# Sheet_1_2023-06-20.net
KiCad netlist of a schematic drawn in Altium Designer
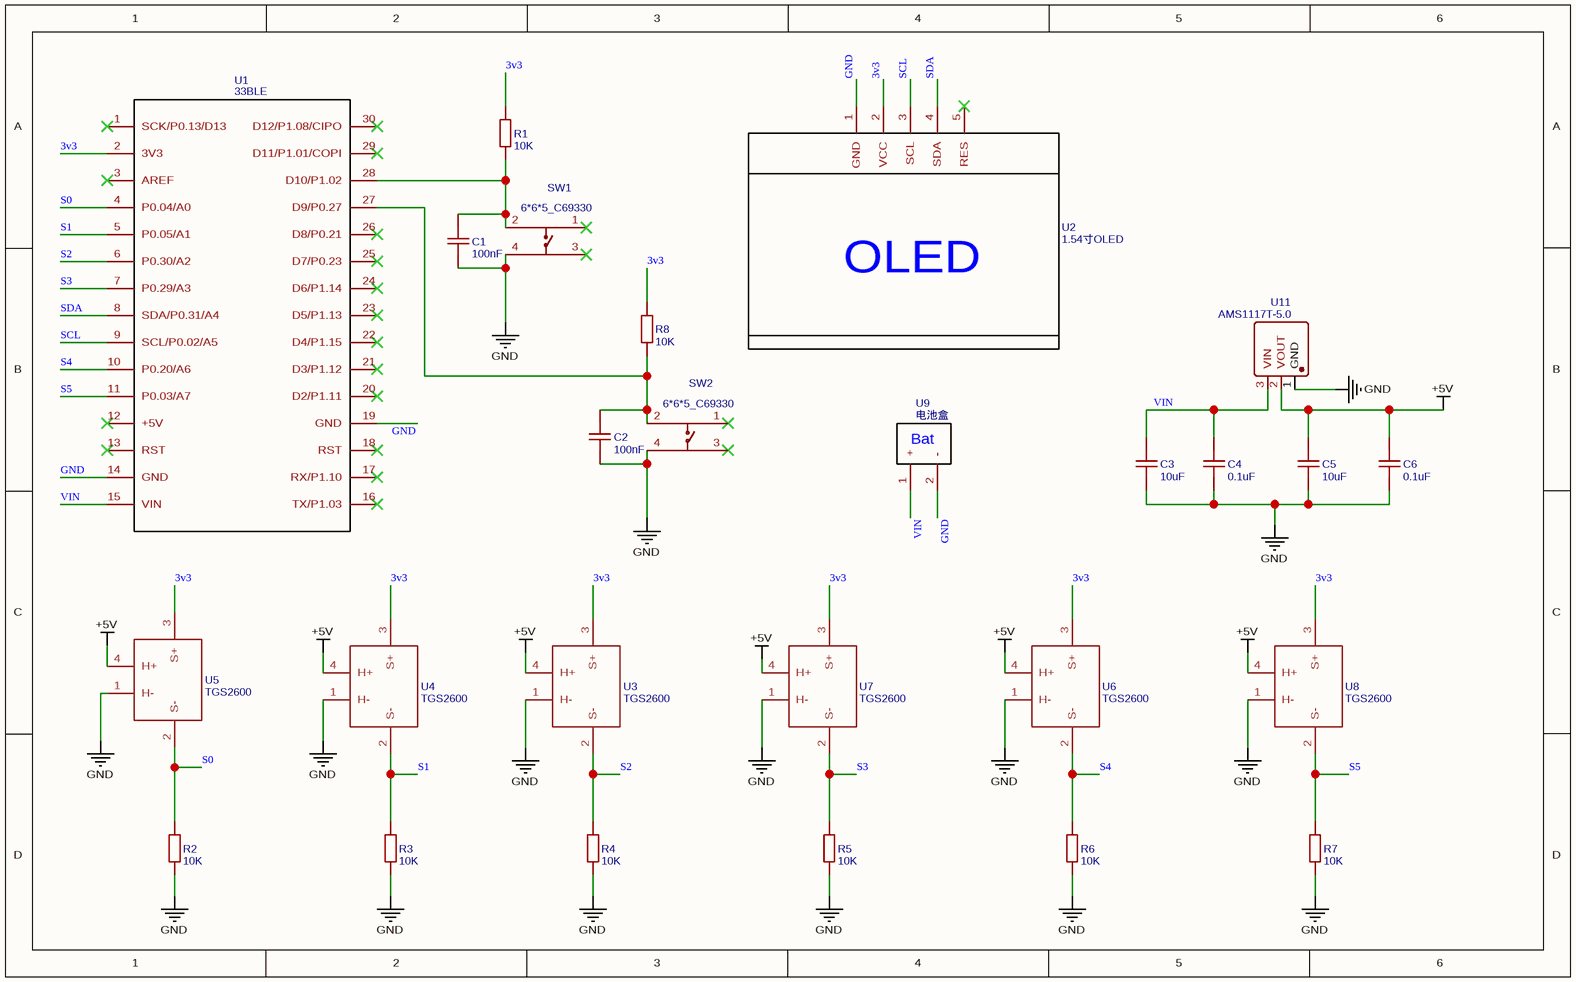
[diagram p0: Sheet_1_2023-06-20.schdoc]

(export (version "E")
  (design (tool "Eeschema 10.0.6"))
  (components
    (comp (ref "C1")
      (value "100nF")
      (fields
        (field (name "BOM_SUPPLIER PART") "C366739")
        (field (name "BOM_MANUFACTURER PART") "F06F1B104MQ0T0SHN0")
        (field (name "CONTRIBUTOR") "LCSC")
      )
      (libsource (lib "altium-import") (part "root_1_100nF_"))
    )
    (comp (ref "C2")
      (value "100nF")
      (fields
        (field (name "BOM_SUPPLIER PART") "C366739")
        (field (name "BOM_MANUFACTURER PART") "F06F1B104MQ0T0SHN0")
        (field (name "CONTRIBUTOR") "LCSC")
      )
      (libsource (lib "altium-import") (part "root_1_100nF_"))
    )
    (comp (ref "C3")
      (value "10uF")
      (fields
        (field (name "BOM_SUPPLIER PART") "C366739")
        (field (name "BOM_MANUFACTURER PART") "F06F1B104MQ0T0SHN0")
        (field (name "CONTRIBUTOR") "LCSC")
      )
      (libsource (lib "altium-import") (part "root_1_10uF_"))
    )
    (comp (ref "C4")
      (value "0.1uF")
      (fields
        (field (name "BOM_SUPPLIER PART") "C366739")
        (field (name "BOM_MANUFACTURER PART") "F06F1B104MQ0T0SHN0")
        (field (name "CONTRIBUTOR") "LCSC")
      )
      (libsource (lib "altium-import") (part "root_1_0.1uF_"))
    )
    (comp (ref "C5")
      (value "10uF")
      (fields
        (field (name "BOM_SUPPLIER PART") "C366739")
        (field (name "BOM_MANUFACTURER PART") "F06F1B104MQ0T0SHN0")
        (field (name "CONTRIBUTOR") "LCSC")
      )
      (libsource (lib "altium-import") (part "root_1_10uF_"))
    )
    (comp (ref "C6")
      (value "0.1uF")
      (fields
        (field (name "BOM_SUPPLIER PART") "C366739")
        (field (name "BOM_MANUFACTURER PART") "F06F1B104MQ0T0SHN0")
        (field (name "CONTRIBUTOR") "LCSC")
      )
      (libsource (lib "altium-import") (part "root_1_0.1uF_"))
    )
    (comp (ref "R1")
      (value "10K")
      (fields
        (field (name "BOM_SUPPLIER PART") "C176401")
        (field (name "BOM_MANUFACTURER PART") "MFR1WSJT-52-10K")
        (field (name "CONTRIBUTOR") "LCSC")
      )
      (libsource (lib "altium-import") (part "root_1_10K_"))
    )
    (comp (ref "R2")
      (value "10K")
      (fields
        (field (name "BOM_SUPPLIER PART") "C176401")
        (field (name "BOM_MANUFACTURER PART") "MFR1WSJT-52-10K")
        (field (name "CONTRIBUTOR") "LCSC")
      )
      (libsource (lib "altium-import") (part "root_1_10K_"))
    )
    (comp (ref "R3")
      (value "10K")
      (fields
        (field (name "BOM_SUPPLIER PART") "C176401")
        (field (name "BOM_MANUFACTURER PART") "MFR1WSJT-52-10K")
        (field (name "CONTRIBUTOR") "LCSC")
      )
      (libsource (lib "altium-import") (part "root_1_10K_"))
    )
    (comp (ref "R4")
      (value "10K")
      (fields
        (field (name "BOM_SUPPLIER PART") "C176401")
        (field (name "BOM_MANUFACTURER PART") "MFR1WSJT-52-10K")
        (field (name "CONTRIBUTOR") "LCSC")
      )
      (libsource (lib "altium-import") (part "root_1_10K_"))
    )
    (comp (ref "R5")
      (value "10K")
      (fields
        (field (name "BOM_SUPPLIER PART") "C176401")
        (field (name "BOM_MANUFACTURER PART") "MFR1WSJT-52-10K")
        (field (name "CONTRIBUTOR") "LCSC")
      )
      (libsource (lib "altium-import") (part "root_1_10K_"))
    )
    (comp (ref "R6")
      (value "10K")
      (fields
        (field (name "BOM_SUPPLIER PART") "C176401")
        (field (name "BOM_MANUFACTURER PART") "MFR1WSJT-52-10K")
        (field (name "CONTRIBUTOR") "LCSC")
      )
      (libsource (lib "altium-import") (part "root_1_10K_"))
    )
    (comp (ref "R7")
      (value "10K")
      (fields
        (field (name "BOM_SUPPLIER PART") "C176401")
        (field (name "BOM_MANUFACTURER PART") "MFR1WSJT-52-10K")
        (field (name "CONTRIBUTOR") "LCSC")
      )
      (libsource (lib "altium-import") (part "root_1_10K_"))
    )
    (comp (ref "R8")
      (value "10K")
      (fields
        (field (name "BOM_SUPPLIER PART") "C176401")
        (field (name "BOM_MANUFACTURER PART") "MFR1WSJT-52-10K")
        (field (name "CONTRIBUTOR") "LCSC")
      )
      (libsource (lib "altium-import") (part "root_1_10K_"))
    )
    (comp (ref "SW1")
      (value "6*6*5_C69330")
      (fields
        (field (name "BOM_MANUFACTURER PART") "6*6*5 直插环保260G 耐温复银")
        (field (name "BOM_SUPPLIER PART") "C69330")
      )
      (libsource (lib "altium-import") (part "root_2_6*6*5_C69330_"))
    )
    (comp (ref "SW2")
      (value "6*6*5_C69330")
      (fields
        (field (name "BOM_MANUFACTURER PART") "6*6*5 直插环保260G 耐温复银")
        (field (name "BOM_SUPPLIER PART") "C69330")
      )
      (libsource (lib "altium-import") (part "root_2_6*6*5_C69330_"))
    )
    (comp (ref "U1")
      (value "33BLE")
      (fields (field (name "CONTRIBUTOR") "jlu_gty"))
      (libsource (lib "altium-import") (part "root_0_33BLE_"))
    )
    (comp (ref "U2")
      (value "1.54寸OLED")
      (fields (field (name "CONTRIBUTOR") "Guest"))
      (libsource (lib "altium-import") (part "root_0_1.54寸OLED_"))
    )
    (comp (ref "U3")
      (value "TGS2600")
      (fields (field (name "BOM_SUPPLIER PART") "C9900008686") (field (name "CONTRIBUTOR") "LCSC"))
      (libsource (lib "altium-import") (part "root_0_TGS2600_"))
    )
    (comp (ref "U4")
      (value "TGS2600")
      (fields (field (name "BOM_SUPPLIER PART") "C9900008686") (field (name "CONTRIBUTOR") "LCSC"))
      (libsource (lib "altium-import") (part "root_0_TGS2600_"))
    )
    (comp (ref "U5")
      (value "TGS2600")
      (fields (field (name "BOM_SUPPLIER PART") "C9900008686") (field (name "CONTRIBUTOR") "LCSC"))
      (libsource (lib "altium-import") (part "root_0_TGS2600_"))
    )
    (comp (ref "U6")
      (value "TGS2600")
      (fields (field (name "BOM_SUPPLIER PART") "C9900008686") (field (name "CONTRIBUTOR") "LCSC"))
      (libsource (lib "altium-import") (part "root_0_TGS2600_"))
    )
    (comp (ref "U7")
      (value "TGS2600")
      (fields (field (name "BOM_SUPPLIER PART") "C9900008686") (field (name "CONTRIBUTOR") "LCSC"))
      (libsource (lib "altium-import") (part "root_0_TGS2600_"))
    )
    (comp (ref "U8")
      (value "TGS2600")
      (fields (field (name "BOM_SUPPLIER PART") "C9900008686") (field (name "CONTRIBUTOR") "LCSC"))
      (libsource (lib "altium-import") (part "root_0_TGS2600_"))
    )
    (comp (ref "U9")
      (value "电池盒")
      (fields (field (name "CONTRIBUTOR") "JLU_GTY"))
      (libsource (lib "altium-import") (part "root_0_电池盒_"))
    )
    (comp (ref "U11")
      (value "AMS1117T-5.0")
      (fields (field (name "BOM_SUPPLIER PART") "C498134") (field (name "CONTRIBUTOR") "LCSC"))
      (libsource (lib "altium-import") (part "root_1_AMS1117T-5.0_"))
    )
  )
  (nets
    (net (code "1") (name "+5V") (class "Default")
      (node (ref "C5") (pin "2") (pinfunction "2_2") (pintype "passive"))
      (node (ref "C6") (pin "2") (pinfunction "2_2") (pintype "passive"))
      (node (ref "U11") (pin "2") (pinfunction "VOUT_2") (pintype "passive"))
      (node (ref "U3") (pin "4") (pinfunction "H+_4") (pintype "passive"))
      (node (ref "U4") (pin "4") (pinfunction "H+_4") (pintype "passive"))
      (node (ref "U5") (pin "4") (pinfunction "H+_4") (pintype "passive"))
      (node (ref "U6") (pin "4") (pinfunction "H+_4") (pintype "passive"))
      (node (ref "U7") (pin "4") (pinfunction "H+_4") (pintype "passive"))
      (node (ref "U8") (pin "4") (pinfunction "H+_4") (pintype "passive"))
    )
    (net (code "2") (name "/3v3") (class "Default")
      (node (ref "R1") (pin "2") (pinfunction "2_2") (pintype "passive"))
      (node (ref "R8") (pin "2") (pinfunction "2_2") (pintype "passive"))
      (node (ref "U1") (pin "2") (pinfunction "3V3_2") (pintype "passive"))
      (node (ref "U2") (pin "2") (pinfunction "VCC_2") (pintype "passive"))
      (node (ref "U3") (pin "3") (pinfunction "S+_3") (pintype "passive"))
      (node (ref "U4") (pin "3") (pinfunction "S+_3") (pintype "passive"))
      (node (ref "U5") (pin "3") (pinfunction "S+_3") (pintype "passive"))
      (node (ref "U6") (pin "3") (pinfunction "S+_3") (pintype "passive"))
      (node (ref "U7") (pin "3") (pinfunction "S+_3") (pintype "passive"))
      (node (ref "U8") (pin "3") (pinfunction "S+_3") (pintype "passive"))
    )
    (net (code "3") (name "/S0") (class "Default")
      (node (ref "R2") (pin "2") (pinfunction "2_2") (pintype "passive"))
      (node (ref "U1") (pin "4") (pinfunction "P0.04/A0_4") (pintype "passive"))
      (node (ref "U5") (pin "2") (pinfunction "S-_2") (pintype "passive"))
    )
    (net (code "4") (name "/S1") (class "Default")
      (node (ref "R3") (pin "2") (pinfunction "2_2") (pintype "passive"))
      (node (ref "U1") (pin "5") (pinfunction "P0.05/A1_5") (pintype "passive"))
      (node (ref "U4") (pin "2") (pinfunction "S-_2") (pintype "passive"))
    )
    (net (code "5") (name "/S2") (class "Default")
      (node (ref "R4") (pin "2") (pinfunction "2_2") (pintype "passive"))
      (node (ref "U1") (pin "6") (pinfunction "P0.30/A2_6") (pintype "passive"))
      (node (ref "U3") (pin "2") (pinfunction "S-_2") (pintype "passive"))
    )
    (net (code "6") (name "/S3") (class "Default")
      (node (ref "R5") (pin "2") (pinfunction "2_2") (pintype "passive"))
      (node (ref "U1") (pin "7") (pinfunction "P0.29/A3_7") (pintype "passive"))
      (node (ref "U7") (pin "2") (pinfunction "S-_2") (pintype "passive"))
    )
    (net (code "7") (name "/S4") (class "Default")
      (node (ref "R6") (pin "2") (pinfunction "2_2") (pintype "passive"))
      (node (ref "U1") (pin "10") (pinfunction "P0.20/A6_10") (pintype "passive"))
      (node (ref "U6") (pin "2") (pinfunction "S-_2") (pintype "passive"))
    )
    (net (code "8") (name "/S5") (class "Default")
      (node (ref "R7") (pin "2") (pinfunction "2_2") (pintype "passive"))
      (node (ref "U1") (pin "11") (pinfunction "P0.03/A7_11") (pintype "passive"))
      (node (ref "U8") (pin "2") (pinfunction "S-_2") (pintype "passive"))
    )
    (net (code "9") (name "/SCL") (class "Default")
      (node (ref "U1") (pin "9") (pinfunction "SCL/P0.02/A5_9") (pintype "passive"))
      (node (ref "U2") (pin "3") (pinfunction "SCL_3") (pintype "passive"))
    )
    (net (code "10") (name "/SDA") (class "Default")
      (node (ref "U1") (pin "8") (pinfunction "SDA/P0.31/A4_8") (pintype "passive"))
      (node (ref "U2") (pin "4") (pinfunction "SDA_4") (pintype "passive"))
    )
    (net (code "11") (name "/VIN") (class "Default")
      (node (ref "C3") (pin "2") (pinfunction "2_2") (pintype "passive"))
      (node (ref "C4") (pin "2") (pinfunction "2_2") (pintype "passive"))
      (node (ref "U1") (pin "15") (pinfunction "VIN_15") (pintype "passive"))
      (node (ref "U11") (pin "3") (pinfunction "VIN_3") (pintype "passive"))
      (node (ref "U9") (pin "1") (pinfunction "+_1") (pintype "passive"))
    )
    (net (code "12") (name "GND") (class "Default")
      (node (ref "C1") (pin "1") (pinfunction "1_1") (pintype "passive"))
      (node (ref "C2") (pin "1") (pinfunction "1_1") (pintype "passive"))
      (node (ref "C3") (pin "1") (pinfunction "1_1") (pintype "passive"))
      (node (ref "C4") (pin "1") (pinfunction "1_1") (pintype "passive"))
      (node (ref "C5") (pin "1") (pinfunction "1_1") (pintype "passive"))
      (node (ref "C6") (pin "1") (pinfunction "1_1") (pintype "passive"))
      (node (ref "R2") (pin "1") (pinfunction "1_1") (pintype "passive"))
      (node (ref "R3") (pin "1") (pinfunction "1_1") (pintype "passive"))
      (node (ref "R4") (pin "1") (pinfunction "1_1") (pintype "passive"))
      (node (ref "R5") (pin "1") (pinfunction "1_1") (pintype "passive"))
      (node (ref "R6") (pin "1") (pinfunction "1_1") (pintype "passive"))
      (node (ref "R7") (pin "1") (pinfunction "1_1") (pintype "passive"))
      (node (ref "SW1") (pin "4") (pinfunction "4_4") (pintype "passive"))
      (node (ref "SW2") (pin "4") (pinfunction "4_4") (pintype "passive"))
      (node (ref "U1") (pin "14") (pinfunction "GND_14") (pintype "passive"))
      (node (ref "U1") (pin "19") (pinfunction "GND_19") (pintype "passive"))
      (node (ref "U11") (pin "1") (pinfunction "GND_1") (pintype "passive"))
      (node (ref "U2") (pin "1") (pinfunction "GND_1") (pintype "passive"))
      (node (ref "U3") (pin "1") (pinfunction "H-_1") (pintype "passive"))
      (node (ref "U4") (pin "1") (pinfunction "H-_1") (pintype "passive"))
      (node (ref "U5") (pin "1") (pinfunction "H-_1") (pintype "passive"))
      (node (ref "U6") (pin "1") (pinfunction "H-_1") (pintype "passive"))
      (node (ref "U7") (pin "1") (pinfunction "H-_1") (pintype "passive"))
      (node (ref "U8") (pin "1") (pinfunction "H-_1") (pintype "passive"))
      (node (ref "U9") (pin "2") (pinfunction "-_2") (pintype "passive"))
    )
    (net (code "13") (name "Net-(U1-D9{slash}P0.27)") (class "Default")
      (node (ref "C2") (pin "2") (pinfunction "2_2") (pintype "passive"))
      (node (ref "R8") (pin "1") (pinfunction "1_1") (pintype "passive"))
      (node (ref "SW2") (pin "2") (pinfunction "2_2") (pintype "passive"))
      (node (ref "U1") (pin "27") (pinfunction "D9/P0.27_27") (pintype "passive"))
    )
    (net (code "14") (name "Net-(U1-D10{slash}P1.02)") (class "Default")
      (node (ref "C1") (pin "2") (pinfunction "2_2") (pintype "passive"))
      (node (ref "R1") (pin "1") (pinfunction "1_1") (pintype "passive"))
      (node (ref "SW1") (pin "2") (pinfunction "2_2") (pintype "passive"))
      (node (ref "U1") (pin "28") (pinfunction "D10/P1.02_28") (pintype "passive"))
    )
    (net (code "15") (name "unconnected-(SW1-Pad1)") (class "Default")
      (node (ref "SW1") (pin "1") (pinfunction "1_1") (pintype "passive+no_connect"))
    )
    (net (code "16") (name "unconnected-(SW1-Pad3)") (class "Default")
      (node (ref "SW1") (pin "3") (pinfunction "3_3") (pintype "passive+no_connect"))
    )
    (net (code "17") (name "unconnected-(SW2-Pad1)") (class "Default")
      (node (ref "SW2") (pin "1") (pinfunction "1_1") (pintype "passive+no_connect"))
    )
    (net (code "18") (name "unconnected-(SW2-Pad3)") (class "Default")
      (node (ref "SW2") (pin "3") (pinfunction "3_3") (pintype "passive+no_connect"))
    )
    (net (code "19") (name "unconnected-(U1-+5V-Pad12)") (class "Default")
      (node (ref "U1") (pin "12") (pinfunction "+5V_12") (pintype "passive+no_connect"))
    )
    (net (code "20") (name "unconnected-(U1-AREF-Pad3)") (class "Default")
      (node (ref "U1") (pin "3") (pinfunction "AREF_3") (pintype "passive+no_connect"))
    )
    (net (code "21") (name "unconnected-(U1-D2{slash}P1.11-Pad20)") (class "Default")
      (node (ref "U1") (pin "20") (pinfunction "D2/P1.11_20") (pintype "passive+no_connect"))
    )
    (net (code "22") (name "unconnected-(U1-D3{slash}P1.12-Pad21)") (class "Default")
      (node (ref "U1") (pin "21") (pinfunction "D3/P1.12_21") (pintype "passive+no_connect"))
    )
    (net (code "23") (name "unconnected-(U1-D4{slash}P1.15-Pad22)") (class "Default")
      (node (ref "U1") (pin "22") (pinfunction "D4/P1.15_22") (pintype "passive+no_connect"))
    )
    (net (code "24") (name "unconnected-(U1-D5{slash}P1.13-Pad23)") (class "Default")
      (node (ref "U1") (pin "23") (pinfunction "D5/P1.13_23") (pintype "passive+no_connect"))
    )
    (net (code "25") (name "unconnected-(U1-D6{slash}P1.14-Pad24)") (class "Default")
      (node (ref "U1") (pin "24") (pinfunction "D6/P1.14_24") (pintype "passive+no_connect"))
    )
    (net (code "26") (name "unconnected-(U1-D7{slash}P0.23-Pad25)") (class "Default")
      (node (ref "U1") (pin "25") (pinfunction "D7/P0.23_25") (pintype "passive+no_connect"))
    )
    (net (code "27") (name "unconnected-(U1-D8{slash}P0.21-Pad26)") (class "Default")
      (node (ref "U1") (pin "26") (pinfunction "D8/P0.21_26") (pintype "passive+no_connect"))
    )
    (net (code "28") (name "unconnected-(U1-D11{slash}P1.01{slash}COPI-Pad29)") (class "Default")
      (node (ref "U1") (pin "29") (pinfunction "D11/P1.01/COPI_29") (pintype "passive+no_connect"))
    )
    (net (code "29") (name "unconnected-(U1-D12{slash}P1.08{slash}CIPO-Pad30)") (class "Default")
      (node (ref "U1") (pin "30") (pinfunction "D12/P1.08/CIPO_30") (pintype "passive+no_connect"))
    )
    (net (code "30") (name "unconnected-(U1-RST-Pad13)") (class "Default")
      (node (ref "U1") (pin "13") (pinfunction "RST_13") (pintype "passive+no_connect"))
    )
    (net (code "31") (name "unconnected-(U1-RST-Pad18)") (class "Default")
      (node (ref "U1") (pin "18") (pinfunction "RST_18") (pintype "passive+no_connect"))
    )
    (net (code "32") (name "unconnected-(U1-RX{slash}P1.10-Pad17)") (class "Default")
      (node (ref "U1") (pin "17") (pinfunction "RX/P1.10_17") (pintype "passive+no_connect"))
    )
    (net (code "33") (name "unconnected-(U1-SCK{slash}P0.13{slash}D13-Pad1)") (class "Default")
      (node (ref "U1") (pin "1") (pinfunction "SCK/P0.13/D13_1") (pintype "passive+no_connect"))
    )
    (net (code "34") (name "unconnected-(U1-TX{slash}P1.03-Pad16)") (class "Default")
      (node (ref "U1") (pin "16") (pinfunction "TX/P1.03_16") (pintype "passive+no_connect"))
    )
    (net (code "35") (name "unconnected-(U2-RES-Pad5)") (class "Default")
      (node (ref "U2") (pin "5") (pinfunction "RES_5") (pintype "passive+no_connect"))
    )
  )
)
